# jtag.net
KiCad netlist of a schematic drawn in Altium Designer
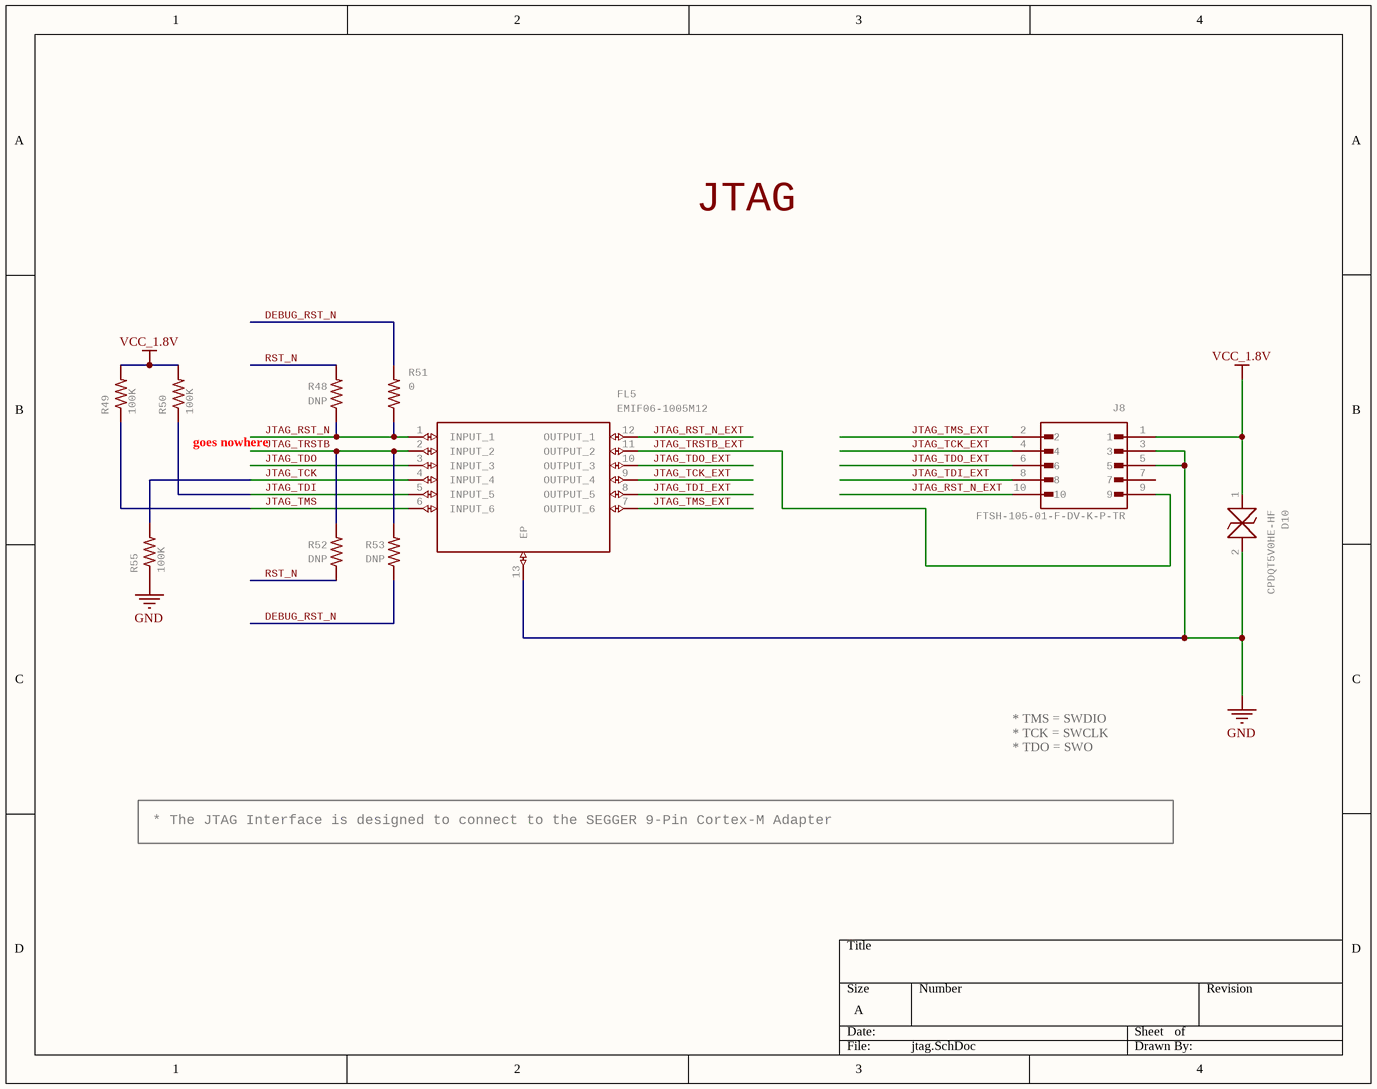
[diagram p0: jtag.SchDoc]

(export (version "E")
  (design (tool "Eeschema 10.0.6"))
  (components
    (comp (ref "D10")
      (value "CPDQT5V0HE-HF")
      (footprint "CPDQT5V0HEHF")
      (description "ESD Suppressors / TVS Diodes DIODE ESD 5VWM 65W 0402/SOD-923F   Source:  Datasheet")
      (fields (field (name "MOUSER_PART_NUMBER") "MOUSER_PART_NUMBER"))
      (libsource (lib "openmv-ae3") (part "CPDQT5V0HE-HF"))
    )
    (comp (ref "FL5")
      (value "EMIF06-1005M12")
      (footprint "SON40P150X250X65-13N")
      (description "EMI Filter Circuits 6lin lw cpcitnc EMI 45pF -35db @ 900MHz   Source:  Datasheet")
      (fields (field (name "MOUSER_PART_NUMBER") "511-EMIF06-1005M12"))
      (libsource (lib "openmv-ae3") (part "EMIF06-1005M12"))
    )
    (comp (ref "J8")
      (value "FTSH-105-01-F-DV-K-P-TR")
      (footprint "CNC_3221-10-0300-00")
      (description "Check availability")
      (fields (field (name "MF") "CNC Tech"))
      (libsource (lib "openmv-ae3") (part "3221-10-0300-00"))
    )
    (comp (ref "R48")
      (value "DNP")
      (footprint "0402-RES")
      (description "ResistorBasic schematic elements and footprints for 0603, 1206, and PTH resistors.")
      (fields (field (name "LIBRARYNAME") "sfe"))
      (libsource (lib "openmv-ae3") (part "RESISTOR0402-RES"))
    )
    (comp (ref "R49")
      (value "100K")
      (footprint "R0201")
      (fields (field (name "LIBRARYNAME") "sfe"))
      (libsource (lib "openmv-ae3") (part "RESISTOR0402-RES"))
    )
    (comp (ref "R50")
      (value "100K")
      (footprint "R0201")
      (fields (field (name "LIBRARYNAME") "sfe"))
      (libsource (lib "openmv-ae3") (part "RESISTOR0402-RES"))
    )
    (comp (ref "R51")
      (value "0")
      (footprint "0402-RES")
      (description "ResistorBasic schematic elements and footprints for 0603, 1206, and PTH resistors.")
      (fields (field (name "MPN") "RC0402JR-070R") (field (name "LIBRARYNAME") "sfe"))
      (libsource (lib "openmv-ae3") (part "RESISTOR0402-RES"))
    )
    (comp (ref "R52")
      (value "DNP")
      (footprint "0402-RES")
      (description "ResistorBasic schematic elements and footprints for 0603, 1206, and PTH resistors.")
      (fields (field (name "LIBRARYNAME") "sfe"))
      (libsource (lib "openmv-ae3") (part "RESISTOR0402-RES"))
    )
    (comp (ref "R53")
      (value "DNP")
      (footprint "0402-RES")
      (description "ResistorBasic schematic elements and footprints for 0603, 1206, and PTH resistors.")
      (fields (field (name "LIBRARYNAME") "sfe"))
      (libsource (lib "openmv-ae3") (part "RESISTOR0402-RES"))
    )
    (comp (ref "R55")
      (value "100K")
      (footprint "R0201")
      (fields (field (name "LIBRARYNAME") "sfe"))
      (libsource (lib "openmv-ae3") (part "RESISTOR0402-RES"))
    )
  )
  (nets
    (net (code "1") (name "/DEBUG_RST_N") (class "Default")
      (node (ref "R51") (pin "2") (pinfunction "2_2") (pintype "passive"))
      (node (ref "R53") (pin "1") (pinfunction "1_1") (pintype "passive"))
    )
    (net (code "2") (name "/JTAG_RST_N") (class "Default")
      (node (ref "FL5") (pin "1") (pinfunction "INPUT_1_1") (pintype "bidirectional"))
      (node (ref "R48") (pin "1") (pinfunction "1_1") (pintype "passive"))
      (node (ref "R51") (pin "1") (pinfunction "1_1") (pintype "passive"))
    )
    (net (code "3") (name "/JTAG_RST_N_EXT") (class "Default")
      (node (ref "FL5") (pin "12") (pinfunction "OUTPUT_1_12") (pintype "bidirectional"))
      (node (ref "J8") (pin "10") (pinfunction "10_10") (pintype "passive"))
    )
    (net (code "4") (name "/JTAG_TCK") (class "Default")
      (node (ref "FL5") (pin "4") (pinfunction "INPUT_4_4") (pintype "bidirectional"))
      (node (ref "R55") (pin "2") (pinfunction "2_2") (pintype "passive"))
    )
    (net (code "5") (name "/JTAG_TCK_EXT") (class "Default")
      (node (ref "FL5") (pin "9") (pinfunction "OUTPUT_4_9") (pintype "bidirectional"))
      (node (ref "J8") (pin "4") (pinfunction "4_4") (pintype "passive"))
    )
    (net (code "6") (name "/JTAG_TDI") (class "Default")
      (node (ref "FL5") (pin "5") (pinfunction "INPUT_5_5") (pintype "bidirectional"))
      (node (ref "R50") (pin "1") (pinfunction "1_1") (pintype "passive"))
    )
    (net (code "7") (name "/JTAG_TDI_EXT") (class "Default")
      (node (ref "FL5") (pin "8") (pinfunction "OUTPUT_5_8") (pintype "bidirectional"))
      (node (ref "J8") (pin "8") (pinfunction "8_8") (pintype "passive"))
    )
    (net (code "8") (name "/JTAG_TDO") (class "Default")
      (node (ref "FL5") (pin "3") (pinfunction "INPUT_3_3") (pintype "bidirectional"))
    )
    (net (code "9") (name "/JTAG_TDO_EXT") (class "Default")
      (node (ref "FL5") (pin "10") (pinfunction "OUTPUT_3_10") (pintype "bidirectional"))
      (node (ref "J8") (pin "6") (pinfunction "6_6") (pintype "passive"))
    )
    (net (code "10") (name "/JTAG_TMS") (class "Default")
      (node (ref "FL5") (pin "6") (pinfunction "INPUT_6_6") (pintype "bidirectional"))
      (node (ref "R49") (pin "1") (pinfunction "1_1") (pintype "passive"))
    )
    (net (code "11") (name "/JTAG_TMS_EXT") (class "Default")
      (node (ref "FL5") (pin "7") (pinfunction "OUTPUT_6_7") (pintype "bidirectional"))
      (node (ref "J8") (pin "2") (pinfunction "2_2") (pintype "passive"))
    )
    (net (code "12") (name "/JTAG_TRSTB") (class "Default")
      (node (ref "FL5") (pin "2") (pinfunction "INPUT_2_2") (pintype "bidirectional"))
      (node (ref "R52") (pin "2") (pinfunction "2_2") (pintype "passive"))
      (node (ref "R53") (pin "2") (pinfunction "2_2") (pintype "passive"))
    )
    (net (code "13") (name "/JTAG_TRSTB_EXT") (class "Default")
      (node (ref "FL5") (pin "11") (pinfunction "OUTPUT_2_11") (pintype "bidirectional"))
      (node (ref "J8") (pin "9") (pinfunction "9_9") (pintype "passive"))
    )
    (net (code "14") (name "/RST_N") (class "Default")
      (node (ref "R48") (pin "2") (pinfunction "2_2") (pintype "passive"))
      (node (ref "R52") (pin "1") (pinfunction "1_1") (pintype "passive"))
    )
    (net (code "15") (name "GND") (class "Default")
      (node (ref "D10") (pin "2") (pinfunction "2_2") (pintype "bidirectional"))
      (node (ref "FL5") (pin "13") (pinfunction "EP_13") (pintype "bidirectional"))
      (node (ref "J8") (pin "3") (pinfunction "3_3") (pintype "passive"))
      (node (ref "J8") (pin "5") (pinfunction "5_5") (pintype "passive"))
      (node (ref "R55") (pin "1") (pinfunction "1_1") (pintype "passive"))
    )
    (net (code "16") (name "VCC_1.8V") (class "Default")
      (node (ref "D10") (pin "1") (pinfunction "1_1") (pintype "bidirectional"))
      (node (ref "J8") (pin "1") (pinfunction "1_1") (pintype "passive"))
      (node (ref "R49") (pin "2") (pinfunction "2_2") (pintype "passive"))
      (node (ref "R50") (pin "2") (pinfunction "2_2") (pintype "passive"))
    )
    (net (code "17") (name "unconnected-(J8-Pad7)") (class "Default")
      (node (ref "J8") (pin "7") (pinfunction "7_7") (pintype "passive"))
    )
  )
)
